# Cargador.net
KiCad netlist of a schematic drawn in Altium Designer
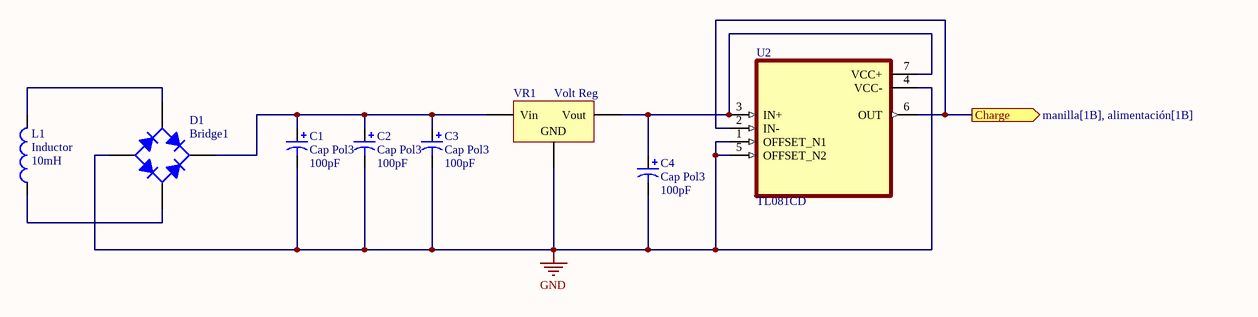
[diagram p0: Cargador.SchDoc]

(export (version "E")
  (design (tool "Eeschema 10.0.6"))
  (components
    (comp (ref "C1")
      (value "Cap Pol3")
      (footprint "C0805")
      (description "Polarized Capacitor (Surface Mount)")
      (fields (field (name "ALTIUM_VALUE") "100pF") (field (name "PUBLISHER") "Altium Limited"))
      (libsource (lib "Miscellaneous Devices") (part "Cap Pol3"))
    )
    (comp (ref "C2")
      (value "Cap Pol3")
      (footprint "C0805")
      (description "Polarized Capacitor (Surface Mount)")
      (fields (field (name "ALTIUM_VALUE") "100pF") (field (name "PUBLISHER") "Altium Limited"))
      (libsource (lib "Miscellaneous Devices") (part "Cap Pol3"))
    )
    (comp (ref "C3")
      (value "Cap Pol3")
      (footprint "C0805")
      (description "Polarized Capacitor (Surface Mount)")
      (fields (field (name "ALTIUM_VALUE") "100pF") (field (name "PUBLISHER") "Altium Limited"))
      (libsource (lib "Miscellaneous Devices") (part "Cap Pol3"))
    )
    (comp (ref "C4")
      (value "Cap Pol3")
      (footprint "C0805")
      (description "Polarized Capacitor (Surface Mount)")
      (fields (field (name "ALTIUM_VALUE") "100pF") (field (name "PUBLISHER") "Altium Limited"))
      (libsource (lib "Miscellaneous Devices") (part "Cap Pol3"))
    )
    (comp (ref "D1")
      (value "Bridge1")
      (footprint "D-38")
      (description "Full Wave Diode Bridge")
      (fields (field (name "PUBLISHER") "Altium Limited"))
      (libsource (lib "Miscellaneous Devices") (part "Bridge1"))
    )
    (comp (ref "L1")
      (value "Inductor")
      (footprint "0402-A")
      (fields (field (name "ALTIUM_VALUE") "10mH") (field (name "PUBLISHER") "Altium Limited"))
      (libsource (lib "Miscellaneous Devices") (part "Inductor"))
    )
    (comp (ref "U2")
      (value "TL081CD")
      (footprint "SOIC127P599X175-8N:SOIC127P599X175-8N")
      (description "High Slew Rate JFET-Input Operational Amplifier 8-SOIC 0 to 70")
      (fields (field (name "MF") "Texas Instruments"))
      (libsource (lib "TL081CD") (part "TL081CD"))
    )
    (comp (ref "VR1")
      (value "Volt Reg")
      (footprint "D2PAK_M")
      (description "Voltage Regulator")
      (fields (field (name "PUBLISHER") "Altium Limited"))
      (libsource (lib "Miscellaneous Devices") (part "Volt Reg"))
    )
  )
  (nets
    (net (code "1") (name "/Charge") (class "Default")
      (node (ref "U2") (pin "2") (pinfunction "IN-_2") (pintype "input"))
      (node (ref "U2") (pin "6") (pinfunction "OUT_6") (pintype "output"))
    )
    (net (code "2") (name "GND") (class "Default")
      (node (ref "C1") (pin "2") (pinfunction "2_2") (pintype "passive"))
      (node (ref "C2") (pin "2") (pinfunction "2_2") (pintype "passive"))
      (node (ref "C3") (pin "2") (pinfunction "2_2") (pintype "passive"))
      (node (ref "C4") (pin "2") (pinfunction "2_2") (pintype "passive"))
      (node (ref "D1") (pin "3") (pinfunction "A_3") (pintype "passive"))
      (node (ref "U2") (pin "1") (pinfunction "OFFSET_N1_1") (pintype "input"))
      (node (ref "U2") (pin "4") (pinfunction "VCC-_4") (pintype "power_in"))
      (node (ref "U2") (pin "5") (pinfunction "OFFSET_N2_5") (pintype "input"))
      (node (ref "VR1") (pin "2") (pinfunction "GND_2") (pintype "passive"))
    )
    (net (code "3") (name "Net-(D1-C-Pad2)") (class "Default")
      (node (ref "D1") (pin "2") (pinfunction "C_2") (pintype "passive"))
      (node (ref "L1") (pin "1") (pinfunction "1_1") (pintype "passive"))
    )
    (net (code "4") (name "Net-(D1-C-Pad4)") (class "Default")
      (node (ref "D1") (pin "4") (pinfunction "C_4") (pintype "passive"))
      (node (ref "L1") (pin "2") (pinfunction "2_2") (pintype "passive"))
    )
    (net (code "5") (name "Net-(D1-K)") (class "Default")
      (node (ref "C1") (pin "1") (pinfunction "1_1") (pintype "passive"))
      (node (ref "C2") (pin "1") (pinfunction "1_1") (pintype "passive"))
      (node (ref "C3") (pin "1") (pinfunction "1_1") (pintype "passive"))
      (node (ref "D1") (pin "1") (pinfunction "K_1") (pintype "passive"))
      (node (ref "VR1") (pin "1") (pinfunction "Vin_1") (pintype "passive"))
    )
    (net (code "6") (name "Net-(U2-IN+)") (class "Default")
      (node (ref "C4") (pin "1") (pinfunction "1_1") (pintype "passive"))
      (node (ref "U2") (pin "3") (pinfunction "IN+_3") (pintype "input"))
      (node (ref "U2") (pin "7") (pinfunction "VCC+_7") (pintype "power_in"))
      (node (ref "VR1") (pin "3") (pinfunction "Vout_3") (pintype "passive"))
    )
  )
)
